# os2.net
KiCad netlist of a schematic drawn in EAGLE
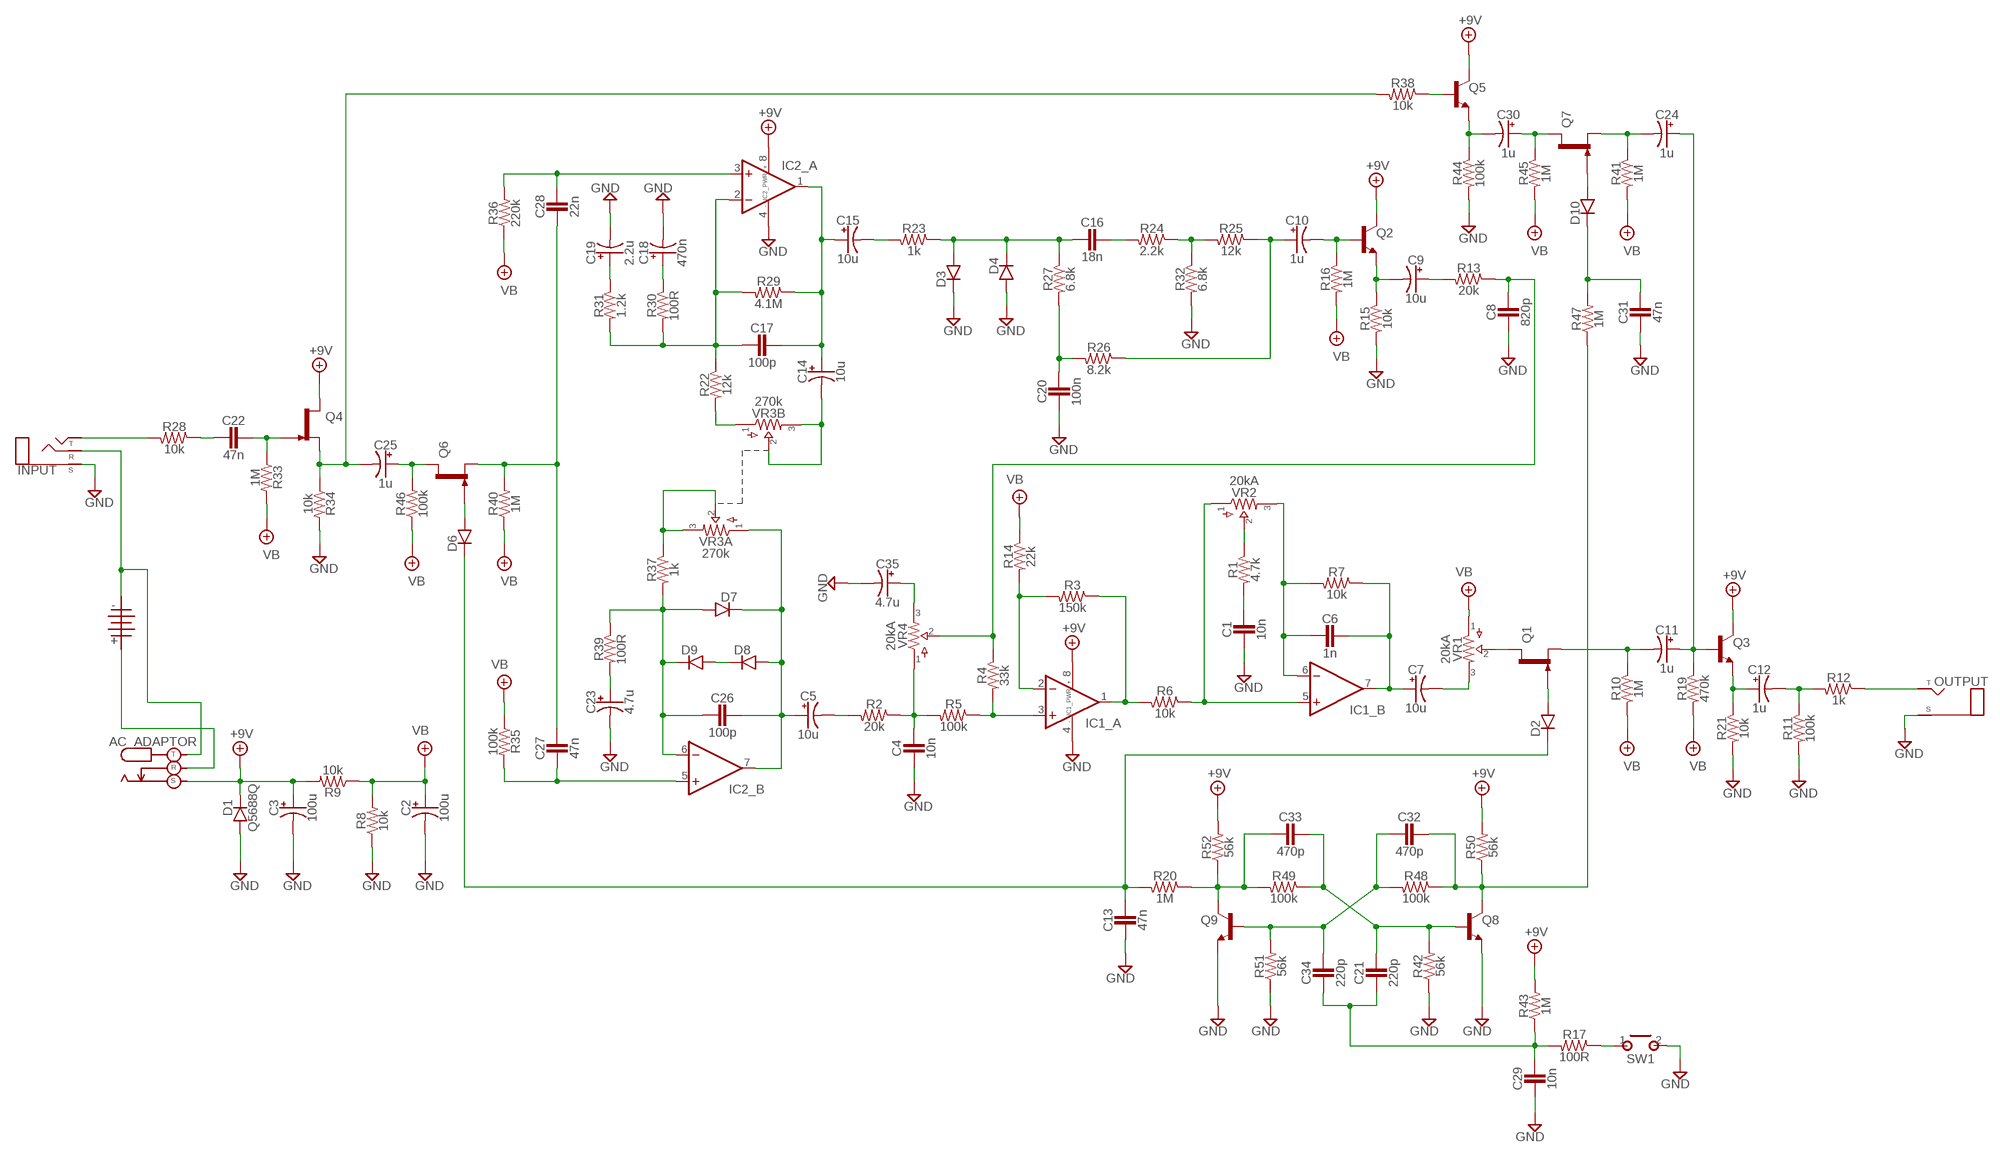
[diagram p0: schematic, sheet 1]

(export (version "E")
  (design (tool "Eeschema 10.0.6"))
  (components
    (comp (ref "1101")
      (value "BATTERY")
      (footprint "eagle-import:TWO_PADS")
      (libsource (lib "eagle-import") (part "BATTERY"))
    )
    (comp (ref "AC_ADAPTOR")
      (value "DC_KOBICONN")
      (footprint "eagle-import:DC_KOBICONN")
      (libsource (lib "eagle-import") (part "DC_KOBICONN"))
    )
    (comp (ref "C1")
      (value "10n")
      (footprint "eagle-import:BOX_SMALL")
      (libsource (lib "eagle-import") (part "CER/FILMBOX.1"))
    )
    (comp (ref "C2")
      (value "100u")
      (footprint "eagle-import:050_020")
      (libsource (lib "eagle-import") (part "0500"))
    )
    (comp (ref "C3")
      (value "100u")
      (footprint "eagle-import:050_020")
      (libsource (lib "eagle-import") (part "0500"))
    )
    (comp (ref "C4")
      (value "10n")
      (footprint "eagle-import:BOX_SMALL")
      (libsource (lib "eagle-import") (part "CER/FILMBOX.1"))
    )
    (comp (ref "C5")
      (value "10u")
      (footprint "eagle-import:050_020")
      (libsource (lib "eagle-import") (part "0500"))
    )
    (comp (ref "C6")
      (value "1n")
      (footprint "eagle-import:BOX_SMALL")
      (libsource (lib "eagle-import") (part "CER/FILMBOX.1"))
    )
    (comp (ref "C7")
      (value "10u")
      (footprint "eagle-import:050_020")
      (libsource (lib "eagle-import") (part "0500"))
    )
    (comp (ref "C8")
      (value "820p")
      (footprint "eagle-import:BOX_SMALL")
      (libsource (lib "eagle-import") (part "CER/FILMBOX.1"))
    )
    (comp (ref "C9")
      (value "10u")
      (footprint "eagle-import:050_020")
      (libsource (lib "eagle-import") (part "0500"))
    )
    (comp (ref "C10")
      (value "1u")
      (footprint "eagle-import:050_020")
      (libsource (lib "eagle-import") (part "0500"))
    )
    (comp (ref "C11")
      (value "1u")
      (footprint "eagle-import:050_020")
      (libsource (lib "eagle-import") (part "0500"))
    )
    (comp (ref "C12")
      (value "1u")
      (footprint "eagle-import:050_020")
      (libsource (lib "eagle-import") (part "0500"))
    )
    (comp (ref "C13")
      (value "47n")
      (footprint "eagle-import:BOX_SMALL")
      (libsource (lib "eagle-import") (part "CER/FILMBOX.1"))
    )
    (comp (ref "C14")
      (value "10u")
      (footprint "eagle-import:050_020")
      (libsource (lib "eagle-import") (part "0500"))
    )
    (comp (ref "C15")
      (value "10u")
      (footprint "eagle-import:050_020")
      (libsource (lib "eagle-import") (part "0500"))
    )
    (comp (ref "C16")
      (value "18n")
      (footprint "eagle-import:BOX_SMALL")
      (libsource (lib "eagle-import") (part "CER/FILMBOX.1"))
    )
    (comp (ref "C17")
      (value "100p")
      (footprint "eagle-import:BOX_SMALL")
      (libsource (lib "eagle-import") (part "CER/FILMBOX.1"))
    )
    (comp (ref "C18")
      (value "470n")
      (footprint "eagle-import:050_020")
      (libsource (lib "eagle-import") (part "0500"))
    )
    (comp (ref "C19")
      (value "2.2u")
      (footprint "eagle-import:050_020")
      (libsource (lib "eagle-import") (part "0500"))
    )
    (comp (ref "C20")
      (value "100n")
      (footprint "eagle-import:BOX_SMALL")
      (libsource (lib "eagle-import") (part "CER/FILMBOX.1"))
    )
    (comp (ref "C21")
      (value "220p")
      (footprint "eagle-import:BOX_SMALL")
      (libsource (lib "eagle-import") (part "CER/FILMBOX.1"))
    )
    (comp (ref "C22")
      (value "47n")
      (footprint "eagle-import:BOX_SMALL")
      (libsource (lib "eagle-import") (part "CER/FILMBOX.1"))
    )
    (comp (ref "C23")
      (value "4.7u")
      (footprint "eagle-import:050_020")
      (libsource (lib "eagle-import") (part "0500"))
    )
    (comp (ref "C24")
      (value "1u")
      (footprint "eagle-import:050_020")
      (libsource (lib "eagle-import") (part "0500"))
    )
    (comp (ref "C25")
      (value "1u")
      (footprint "eagle-import:050_020")
      (libsource (lib "eagle-import") (part "0500"))
    )
    (comp (ref "C26")
      (value "100p")
      (footprint "eagle-import:BOX_SMALL")
      (libsource (lib "eagle-import") (part "CER/FILMBOX.1"))
    )
    (comp (ref "C27")
      (value "47n")
      (footprint "eagle-import:BOX_SMALL")
      (libsource (lib "eagle-import") (part "CER/FILMBOX.1"))
    )
    (comp (ref "C28")
      (value "22n")
      (footprint "eagle-import:BOX_SMALL")
      (libsource (lib "eagle-import") (part "CER/FILMBOX.1"))
    )
    (comp (ref "C29")
      (value "10n")
      (footprint "eagle-import:BOX_SMALL")
      (libsource (lib "eagle-import") (part "CER/FILMBOX.1"))
    )
    (comp (ref "C30")
      (value "1u")
      (footprint "eagle-import:050_020")
      (libsource (lib "eagle-import") (part "0500"))
    )
    (comp (ref "C31")
      (value "47n")
      (footprint "eagle-import:BOX_SMALL")
      (libsource (lib "eagle-import") (part "CER/FILMBOX.1"))
    )
    (comp (ref "C32")
      (value "470p")
      (footprint "eagle-import:BOX_SMALL")
      (libsource (lib "eagle-import") (part "CER/FILMBOX.1"))
    )
    (comp (ref "C33")
      (value "470p")
      (footprint "eagle-import:BOX_SMALL")
      (libsource (lib "eagle-import") (part "CER/FILMBOX.1"))
    )
    (comp (ref "C34")
      (value "220p")
      (footprint "eagle-import:BOX_SMALL")
      (libsource (lib "eagle-import") (part "CER/FILMBOX.1"))
    )
    (comp (ref "C35")
      (value "4.7u")
      (footprint "eagle-import:050_020")
      (libsource (lib "eagle-import") (part "0500"))
    )
    (comp (ref "D1")
      (value "Q5688Q")
      (footprint "eagle-import:DO35-2")
      (libsource (lib "eagle-import") (part "DO35.2"))
    )
    (comp (ref "D2")
      (value "DO35.2")
      (footprint "eagle-import:DO35-2")
      (libsource (lib "eagle-import") (part "DO35.2"))
    )
    (comp (ref "D3")
      (value "DO35.2")
      (footprint "eagle-import:DO35-2")
      (libsource (lib "eagle-import") (part "DO35.2"))
    )
    (comp (ref "D4")
      (value "DO35.2")
      (footprint "eagle-import:DO35-2")
      (libsource (lib "eagle-import") (part "DO35.2"))
    )
    (comp (ref "D6")
      (value "DO35.2")
      (footprint "eagle-import:DO35-2")
      (libsource (lib "eagle-import") (part "DO35.2"))
    )
    (comp (ref "D7")
      (value "DO35.2")
      (footprint "eagle-import:DO35-2")
      (libsource (lib "eagle-import") (part "DO35.2"))
    )
    (comp (ref "D8")
      (value "DO35.2")
      (footprint "eagle-import:DO35-2")
      (libsource (lib "eagle-import") (part "DO35.2"))
    )
    (comp (ref "D9")
      (value "DO35.2")
      (footprint "eagle-import:DO35-2")
      (libsource (lib "eagle-import") (part "DO35.2"))
    )
    (comp (ref "D10")
      (value "DO35.2")
      (footprint "eagle-import:DO35-2")
      (libsource (lib "eagle-import") (part "DO35.2"))
    )
    (comp (ref "IC1")
      (value "DUALTH")
      (footprint "eagle-import:DIL0")
      (libsource (lib "eagle-import") (part "DUALTH"))
    )
    (comp (ref "IC2")
      (value "DUALTH")
      (footprint "eagle-import:DIL0")
      (libsource (lib "eagle-import") (part "DUALTH"))
    )
    (comp (ref "INPUT")
      (value "STEREO3PADS")
      (footprint "eagle-import:THREEPADS")
      (libsource (lib "eagle-import") (part "STEREO3PADS"))
    )
    (comp (ref "OUTPUT")
      (value "MONO")
      (footprint "eagle-import:TWO_PADS")
      (libsource (lib "eagle-import") (part "MONO"))
    )
    (comp (ref "Q1")
      (value "2N5457")
      (footprint "eagle-import:TO92-")
      (libsource (lib "eagle-import") (part "2N5457"))
    )
    (comp (ref "Q2")
      (value "2SC828A")
      (footprint "eagle-import:TO92-")
      (libsource (lib "eagle-import") (part "2SC828A"))
    )
    (comp (ref "Q3")
      (value "2SC828A")
      (footprint "eagle-import:TO92-")
      (libsource (lib "eagle-import") (part "2SC828A"))
    )
    (comp (ref "Q4")
      (value "2N5457")
      (footprint "eagle-import:TO92-")
      (libsource (lib "eagle-import") (part "2N5457"))
    )
    (comp (ref "Q5")
      (value "2SC828A")
      (footprint "eagle-import:TO92-")
      (libsource (lib "eagle-import") (part "2SC828A"))
    )
    (comp (ref "Q6")
      (value "2N5457")
      (footprint "eagle-import:TO92-")
      (libsource (lib "eagle-import") (part "2N5457"))
    )
    (comp (ref "Q7")
      (value "2N5457")
      (footprint "eagle-import:TO92-")
      (libsource (lib "eagle-import") (part "2N5457"))
    )
    (comp (ref "Q8")
      (value "2SC828A")
      (footprint "eagle-import:TO92-")
      (libsource (lib "eagle-import") (part "2SC828A"))
    )
    (comp (ref "Q9")
      (value "2SC828A")
      (footprint "eagle-import:TO92-")
      (libsource (lib "eagle-import") (part "2SC828A"))
    )
    (comp (ref "R1")
      (value "4.7k")
      (footprint "eagle-import:R0207_3")
      (libsource (lib "eagle-import") (part "R_.3B"))
    )
    (comp (ref "R2")
      (value "20k")
      (footprint "eagle-import:R0207_3")
      (libsource (lib "eagle-import") (part "R_.3B"))
    )
    (comp (ref "R3")
      (value "150k")
      (footprint "eagle-import:R0207_3")
      (libsource (lib "eagle-import") (part "R_.3B"))
    )
    (comp (ref "R4")
      (value "33k")
      (footprint "eagle-import:R0207_3")
      (libsource (lib "eagle-import") (part "R_.3B"))
    )
    (comp (ref "R5")
      (value "100k")
      (footprint "eagle-import:R0207_3")
      (libsource (lib "eagle-import") (part "R_.3B"))
    )
    (comp (ref "R6")
      (value "10k")
      (footprint "eagle-import:R0207_3")
      (libsource (lib "eagle-import") (part "R_.3B"))
    )
    (comp (ref "R7")
      (value "10k")
      (footprint "eagle-import:R0207_3")
      (libsource (lib "eagle-import") (part "R_.3B"))
    )
    (comp (ref "R8")
      (value "10k")
      (footprint "eagle-import:R0207_3")
      (libsource (lib "eagle-import") (part "R_.3B"))
    )
    (comp (ref "R9")
      (value "10k")
      (footprint "eagle-import:R0207_3")
      (libsource (lib "eagle-import") (part "R_.3B"))
    )
    (comp (ref "R10")
      (value "1M")
      (footprint "eagle-import:R0207_3")
      (libsource (lib "eagle-import") (part "R_.3B"))
    )
    (comp (ref "R11")
      (value "100k")
      (footprint "eagle-import:R0207_3")
      (libsource (lib "eagle-import") (part "R_.3B"))
    )
    (comp (ref "R12")
      (value "1k")
      (footprint "eagle-import:R0207_3")
      (libsource (lib "eagle-import") (part "R_.3B"))
    )
    (comp (ref "R13")
      (value "20k")
      (footprint "eagle-import:R0207_3")
      (libsource (lib "eagle-import") (part "R_.3B"))
    )
    (comp (ref "R14")
      (value "22k")
      (footprint "eagle-import:R0207_3")
      (libsource (lib "eagle-import") (part "R_.3B"))
    )
    (comp (ref "R15")
      (value "10k")
      (footprint "eagle-import:R0207_3")
      (libsource (lib "eagle-import") (part "R_.3B"))
    )
    (comp (ref "R16")
      (value "1M")
      (footprint "eagle-import:R0207_3")
      (libsource (lib "eagle-import") (part "R_.3B"))
    )
    (comp (ref "R17")
      (value "100R")
      (footprint "eagle-import:R0207_3")
      (libsource (lib "eagle-import") (part "R_.3B"))
    )
    (comp (ref "R19")
      (value "470k")
      (footprint "eagle-import:R0207_3")
      (libsource (lib "eagle-import") (part "R_.3B"))
    )
    (comp (ref "R20")
      (value "1M")
      (footprint "eagle-import:R0207_3")
      (libsource (lib "eagle-import") (part "R_.3B"))
    )
    (comp (ref "R21")
      (value "10k")
      (footprint "eagle-import:R0207_3")
      (libsource (lib "eagle-import") (part "R_.3B"))
    )
    (comp (ref "R22")
      (value "12k")
      (footprint "eagle-import:R0207_3")
      (libsource (lib "eagle-import") (part "R_.3B"))
    )
    (comp (ref "R23")
      (value "1k")
      (footprint "eagle-import:R0207_3")
      (libsource (lib "eagle-import") (part "R_.3B"))
    )
    (comp (ref "R24")
      (value "2.2k")
      (footprint "eagle-import:R0207_3")
      (libsource (lib "eagle-import") (part "R_.3B"))
    )
    (comp (ref "R25")
      (value "12k")
      (footprint "eagle-import:R0207_3")
      (libsource (lib "eagle-import") (part "R_.3B"))
    )
    (comp (ref "R26")
      (value "8.2k")
      (footprint "eagle-import:R0207_3")
      (libsource (lib "eagle-import") (part "R_.3B"))
    )
    (comp (ref "R27")
      (value "6.8k")
      (footprint "eagle-import:R0207_3")
      (libsource (lib "eagle-import") (part "R_.3B"))
    )
    (comp (ref "R28")
      (value "10k")
      (footprint "eagle-import:R0207_3")
      (libsource (lib "eagle-import") (part "R_.3B"))
    )
    (comp (ref "R29")
      (value "4.1M")
      (footprint "eagle-import:R0207_3")
      (libsource (lib "eagle-import") (part "R_.3B"))
    )
    (comp (ref "R30")
      (value "100R")
      (footprint "eagle-import:R0207_3")
      (libsource (lib "eagle-import") (part "R_.3B"))
    )
    (comp (ref "R31")
      (value "1.2k")
      (footprint "eagle-import:R0207_3")
      (libsource (lib "eagle-import") (part "R_.3B"))
    )
    (comp (ref "R32")
      (value "6.8k")
      (footprint "eagle-import:R0207_3")
      (libsource (lib "eagle-import") (part "R_.3B"))
    )
    (comp (ref "R33")
      (value "1M")
      (footprint "eagle-import:R0207_3")
      (libsource (lib "eagle-import") (part "R_.3B"))
    )
    (comp (ref "R34")
      (value "10k")
      (footprint "eagle-import:R0207_3")
      (libsource (lib "eagle-import") (part "R_.3B"))
    )
    (comp (ref "R35")
      (value "100k")
      (footprint "eagle-import:R0207_3")
      (libsource (lib "eagle-import") (part "R_.3B"))
    )
    (comp (ref "R36")
      (value "220k")
      (footprint "eagle-import:R0207_3")
      (libsource (lib "eagle-import") (part "R_.3B"))
    )
    (comp (ref "R37")
      (value "1k")
      (footprint "eagle-import:R0207_3")
      (libsource (lib "eagle-import") (part "R_.3B"))
    )
    (comp (ref "R38")
      (value "10k")
      (footprint "eagle-import:R0207_3")
      (libsource (lib "eagle-import") (part "R_.3B"))
    )
    (comp (ref "R39")
      (value "100R")
      (footprint "eagle-import:R0207_3")
      (libsource (lib "eagle-import") (part "R_.3B"))
    )
    (comp (ref "R40")
      (value "1M")
      (footprint "eagle-import:R0207_3")
      (libsource (lib "eagle-import") (part "R_.3B"))
    )
    (comp (ref "R41")
      (value "1M")
      (footprint "eagle-import:R0207_3")
      (libsource (lib "eagle-import") (part "R_.3B"))
    )
    (comp (ref "R42")
      (value "56k")
      (footprint "eagle-import:R0207_3")
      (libsource (lib "eagle-import") (part "R_.3B"))
    )
    (comp (ref "R43")
      (value "1M")
      (footprint "eagle-import:R0207_3")
      (libsource (lib "eagle-import") (part "R_.3B"))
    )
    (comp (ref "R44")
      (value "100k")
      (footprint "eagle-import:R0207_3")
      (libsource (lib "eagle-import") (part "R_.3B"))
    )
    (comp (ref "R45")
      (value "1M")
      (footprint "eagle-import:R0207_3")
      (libsource (lib "eagle-import") (part "R_.3B"))
    )
    (comp (ref "R46")
      (value "100k")
      (footprint "eagle-import:R0207_3")
      (libsource (lib "eagle-import") (part "R_.3B"))
    )
    (comp (ref "R47")
      (value "1M")
      (footprint "eagle-import:R0207_3")
      (libsource (lib "eagle-import") (part "R_.3B"))
    )
    (comp (ref "R48")
      (value "100k")
      (footprint "eagle-import:R0207_3")
      (libsource (lib "eagle-import") (part "R_.3B"))
    )
    (comp (ref "R49")
      (value "100k")
      (footprint "eagle-import:R0207_3")
      (libsource (lib "eagle-import") (part "R_.3B"))
    )
    (comp (ref "R50")
      (value "56k")
      (footprint "eagle-import:R0207_3")
      (libsource (lib "eagle-import") (part "R_.3B"))
    )
    (comp (ref "R51")
      (value "56k")
      (footprint "eagle-import:R0207_3")
      (libsource (lib "eagle-import") (part "R_.3B"))
    )
    (comp (ref "R52")
      (value "56k")
      (footprint "eagle-import:R0207_3")
      (libsource (lib "eagle-import") (part "R_.3B"))
    )
    (comp (ref "SW1")
      (value "MOMENTARY")
      (footprint "eagle-import:SPST")
      (libsource (lib "eagle-import") (part "MOMENTARY"))
    )
    (comp (ref "VR1")
      (value "20kA")
      (footprint "eagle-import:16MM")
      (libsource (lib "eagle-import") (part "POTS16MM"))
    )
    (comp (ref "VR2")
      (value "20kA")
      (footprint "eagle-import:16MM")
      (libsource (lib "eagle-import") (part "POTS16MM"))
    )
    (comp (ref "VR3A")
      (value "270k")
      (footprint "eagle-import:16MM")
      (libsource (lib "eagle-import") (part "POTS16MM"))
    )
    (comp (ref "VR3B")
      (value "270k")
      (footprint "eagle-import:16MM")
      (libsource (lib "eagle-import") (part "POTS16MM"))
    )
    (comp (ref "VR4")
      (value "20kA")
      (footprint "eagle-import:16MM")
      (libsource (lib "eagle-import") (part "POTS16MM"))
    )
  )
  (nets
    (net (code "1") (name "+9V") (class "Default")
      (node (ref "AC_ADAPTOR") (pin "S") (pinfunction "S_S") (pintype "bidirectional"))
      (node (ref "C3") (pin "+") (pinfunction "+_+") (pintype "passive"))
      (node (ref "D1") (pin "C") (pinfunction "C_C") (pintype "passive"))
      (node (ref "IC1") (pin "8") (pinfunction "V+_8") (pintype "power_in"))
      (node (ref "IC2") (pin "8") (pinfunction "V+_8") (pintype "power_in"))
      (node (ref "Q2") (pin "2") (pinfunction "C_2") (pintype "passive"))
      (node (ref "Q3") (pin "2") (pinfunction "C_2") (pintype "passive"))
      (node (ref "Q4") (pin "3") (pinfunction "D_3") (pintype "passive"))
      (node (ref "Q5") (pin "2") (pinfunction "C_2") (pintype "passive"))
      (node (ref "R43") (pin "2") (pinfunction "2_2") (pintype "passive"))
      (node (ref "R50") (pin "2") (pinfunction "2_2") (pintype "passive"))
      (node (ref "R52") (pin "2") (pinfunction "2_2") (pintype "passive"))
      (node (ref "R9") (pin "2") (pinfunction "2_2") (pintype "passive"))
    )
    (net (code "2") (name "GND") (class "Default")
      (node (ref "C1") (pin "2") (pinfunction "2_2") (pintype "passive"))
      (node (ref "C13") (pin "1") (pinfunction "1_1") (pintype "passive"))
      (node (ref "C18") (pin "-") (pinfunction "-_-") (pintype "passive"))
      (node (ref "C19") (pin "-") (pinfunction "-_-") (pintype "passive"))
      (node (ref "C2") (pin "-") (pinfunction "-_-") (pintype "passive"))
      (node (ref "C20") (pin "2") (pinfunction "2_2") (pintype "passive"))
      (node (ref "C23") (pin "-") (pinfunction "-_-") (pintype "passive"))
      (node (ref "C29") (pin "1") (pinfunction "1_1") (pintype "passive"))
      (node (ref "C3") (pin "-") (pinfunction "-_-") (pintype "passive"))
      (node (ref "C31") (pin "2") (pinfunction "2_2") (pintype "passive"))
      (node (ref "C35") (pin "-") (pinfunction "-_-") (pintype "passive"))
      (node (ref "C4") (pin "2") (pinfunction "2_2") (pintype "passive"))
      (node (ref "C8") (pin "2") (pinfunction "2_2") (pintype "passive"))
      (node (ref "D1") (pin "A") (pinfunction "A_A") (pintype "passive"))
      (node (ref "D3") (pin "C") (pinfunction "C_C") (pintype "passive"))
      (node (ref "D4") (pin "A") (pinfunction "A_A") (pintype "passive"))
      (node (ref "IC1") (pin "4") (pinfunction "V-_4") (pintype "power_in"))
      (node (ref "IC2") (pin "4") (pinfunction "V-_4") (pintype "power_in"))
      (node (ref "INPUT") (pin "SLEEVE") (pinfunction "S_SLEEVE") (pintype "passive"))
      (node (ref "OUTPUT") (pin "S") (pinfunction "SLEEVE_S") (pintype "passive"))
      (node (ref "Q8") (pin "3") (pinfunction "E_3") (pintype "passive"))
      (node (ref "Q9") (pin "3") (pinfunction "E_3") (pintype "passive"))
      (node (ref "R11") (pin "2") (pinfunction "2_2") (pintype "passive"))
      (node (ref "R15") (pin "2") (pinfunction "2_2") (pintype "passive"))
      (node (ref "R21") (pin "2") (pinfunction "2_2") (pintype "passive"))
      (node (ref "R32") (pin "2") (pinfunction "2_2") (pintype "passive"))
      (node (ref "R34") (pin "2") (pinfunction "2_2") (pintype "passive"))
      (node (ref "R42") (pin "1") (pinfunction "1_1") (pintype "passive"))
      (node (ref "R44") (pin "2") (pinfunction "2_2") (pintype "passive"))
      (node (ref "R51") (pin "1") (pinfunction "1_1") (pintype "passive"))
      (node (ref "R8") (pin "1") (pinfunction "1_1") (pintype "passive"))
      (node (ref "SW1") (pin "2") (pinfunction "S_2") (pintype "passive"))
    )
    (net (code "3") (name "Net-(1101-P$1)") (class "Default")
      (node (ref "1101") (pin "T") (pinfunction "P$1_T") (pintype "bidirectional"))
      (node (ref "AC_ADAPTOR") (pin "R") (pinfunction "R_R") (pintype "bidirectional"))
    )
    (net (code "4") (name "Net-(1101-P$2)") (class "Default")
      (node (ref "1101") (pin "S") (pinfunction "P$2_S") (pintype "bidirectional"))
      (node (ref "AC_ADAPTOR") (pin "T") (pinfunction "T_T") (pintype "bidirectional"))
      (node (ref "INPUT") (pin "RING") (pinfunction "R_RING") (pintype "passive"))
    )
    (net (code "5") (name "Net-(C1-Pad1)") (class "Default")
      (node (ref "C1") (pin "1") (pinfunction "1_1") (pintype "passive"))
      (node (ref "R1") (pin "2") (pinfunction "2_2") (pintype "passive"))
    )
    (net (code "6") (name "Net-(C4-Pad1)") (class "Default")
      (node (ref "C4") (pin "1") (pinfunction "1_1") (pintype "passive"))
      (node (ref "R2") (pin "1") (pinfunction "1_1") (pintype "passive"))
      (node (ref "R5") (pin "2") (pinfunction "2_2") (pintype "passive"))
      (node (ref "VR4") (pin "1") (pinfunction "1_1") (pintype "passive"))
    )
    (net (code "7") (name "Net-(C5-Pad-)") (class "Default")
      (node (ref "C5") (pin "-") (pinfunction "-_-") (pintype "passive"))
      (node (ref "R2") (pin "2") (pinfunction "2_2") (pintype "passive"))
    )
    (net (code "8") (name "Net-(C7-Pad-)") (class "Default")
      (node (ref "C7") (pin "-") (pinfunction "-_-") (pintype "passive"))
      (node (ref "VR1") (pin "3") (pinfunction "3_3") (pintype "passive"))
    )
    (net (code "9") (name "Net-(C8-Pad1)") (class "Default")
      (node (ref "C8") (pin "1") (pinfunction "1_1") (pintype "passive"))
      (node (ref "R13") (pin "1") (pinfunction "1_1") (pintype "passive"))
      (node (ref "R4") (pin "1") (pinfunction "1_1") (pintype "passive"))
      (node (ref "VR4") (pin "2") (pinfunction "2_2") (pintype "passive"))
    )
    (net (code "10") (name "Net-(C9-Pad+)") (class "Default")
      (node (ref "C9") (pin "+") (pinfunction "+_+") (pintype "passive"))
      (node (ref "R13") (pin "2") (pinfunction "2_2") (pintype "passive"))
    )
    (net (code "11") (name "Net-(C10-Pad+)") (class "Default")
      (node (ref "C10") (pin "+") (pinfunction "+_+") (pintype "passive"))
      (node (ref "R25") (pin "1") (pinfunction "1_1") (pintype "passive"))
      (node (ref "R26") (pin "1") (pinfunction "1_1") (pintype "passive"))
    )
    (net (code "12") (name "Net-(C12-Pad-)") (class "Default")
      (node (ref "C12") (pin "-") (pinfunction "-_-") (pintype "passive"))
      (node (ref "R11") (pin "1") (pinfunction "1_1") (pintype "passive"))
      (node (ref "R12") (pin "2") (pinfunction "2_2") (pintype "passive"))
    )
    (net (code "13") (name "Net-(C13-Pad2)") (class "Default")
      (node (ref "C13") (pin "2") (pinfunction "2_2") (pintype "passive"))
      (node (ref "D2") (pin "C") (pinfunction "C_C") (pintype "passive"))
      (node (ref "D6") (pin "C") (pinfunction "C_C") (pintype "passive"))
      (node (ref "R20") (pin "2") (pinfunction "2_2") (pintype "passive"))
    )
    (net (code "14") (name "Net-(C14-Pad-)") (class "Default")
      (node (ref "C14") (pin "-") (pinfunction "-_-") (pintype "passive"))
      (node (ref "VR3B") (pin "2") (pinfunction "2_2") (pintype "passive"))
      (node (ref "VR3B") (pin "3") (pinfunction "3_3") (pintype "passive"))
    )
    (net (code "15") (name "Net-(C15-Pad-)") (class "Default")
      (node (ref "C15") (pin "-") (pinfunction "-_-") (pintype "passive"))
      (node (ref "R23") (pin "2") (pinfunction "2_2") (pintype "passive"))
    )
    (net (code "16") (name "Net-(C16-Pad1)") (class "Default")
      (node (ref "C16") (pin "1") (pinfunction "1_1") (pintype "passive"))
      (node (ref "R24") (pin "2") (pinfunction "2_2") (pintype "passive"))
    )
    (net (code "17") (name "Net-(C16-Pad2)") (class "Default")
      (node (ref "C16") (pin "2") (pinfunction "2_2") (pintype "passive"))
      (node (ref "D3") (pin "A") (pinfunction "A_A") (pintype "passive"))
      (node (ref "D4") (pin "C") (pinfunction "C_C") (pintype "passive"))
      (node (ref "R23") (pin "1") (pinfunction "1_1") (pintype "passive"))
      (node (ref "R27") (pin "1") (pinfunction "1_1") (pintype "passive"))
    )
    (net (code "18") (name "Net-(C18-Pad+)") (class "Default")
      (node (ref "C18") (pin "+") (pinfunction "+_+") (pintype "passive"))
      (node (ref "R30") (pin "1") (pinfunction "1_1") (pintype "passive"))
    )
    (net (code "19") (name "Net-(C19-Pad+)") (class "Default")
      (node (ref "C19") (pin "+") (pinfunction "+_+") (pintype "passive"))
      (node (ref "R31") (pin "1") (pinfunction "1_1") (pintype "passive"))
    )
    (net (code "20") (name "Net-(C20-Pad1)") (class "Default")
      (node (ref "C20") (pin "1") (pinfunction "1_1") (pintype "passive"))
      (node (ref "R26") (pin "2") (pinfunction "2_2") (pintype "passive"))
      (node (ref "R27") (pin "2") (pinfunction "2_2") (pintype "passive"))
    )
    (net (code "21") (name "Net-(C21-Pad2)") (class "Default")
      (node (ref "C21") (pin "2") (pinfunction "2_2") (pintype "passive"))
      (node (ref "C29") (pin "2") (pinfunction "2_2") (pintype "passive"))
      (node (ref "C34") (pin "2") (pinfunction "2_2") (pintype "passive"))
      (node (ref "R17") (pin "2") (pinfunction "2_2") (pintype "passive"))
      (node (ref "R43") (pin "1") (pinfunction "1_1") (pintype "passive"))
    )
    (net (code "22") (name "Net-(C22-Pad2)") (class "Default")
      (node (ref "C22") (pin "2") (pinfunction "2_2") (pintype "passive"))
      (node (ref "R28") (pin "1") (pinfunction "1_1") (pintype "passive"))
    )
    (net (code "23") (name "Net-(C23-Pad+)") (class "Default")
      (node (ref "C23") (pin "+") (pinfunction "+_+") (pintype "passive"))
      (node (ref "R39") (pin "2") (pinfunction "2_2") (pintype "passive"))
    )
    (net (code "24") (name "Net-(C31-Pad1)") (class "Default")
      (node (ref "C31") (pin "1") (pinfunction "1_1") (pintype "passive"))
      (node (ref "D10") (pin "C") (pinfunction "C_C") (pintype "passive"))
      (node (ref "R47") (pin "2") (pinfunction "2_2") (pintype "passive"))
    )
    (net (code "25") (name "Net-(C35-Pad+)") (class "Default")
      (node (ref "C35") (pin "+") (pinfunction "+_+") (pintype "passive"))
      (node (ref "VR4") (pin "3") (pinfunction "3_3") (pintype "passive"))
    )
    (net (code "26") (name "Net-(D8-PadC)") (class "Default")
      (node (ref "D8") (pin "C") (pinfunction "C_C") (pintype "passive"))
      (node (ref "D9") (pin "A") (pinfunction "A_A") (pintype "passive"))
    )
    (net (code "27") (name "Net-(IC1A-+IN)") (class "Default")
      (node (ref "IC1") (pin "3") (pinfunction "+IN_3") (pintype "input"))
      (node (ref "R4") (pin "2") (pinfunction "2_2") (pintype "passive"))
      (node (ref "R5") (pin "1") (pinfunction "1_1") (pintype "passive"))
    )
    (net (code "28") (name "Net-(IC1A--IN)") (class "Default")
      (node (ref "IC1") (pin "2") (pinfunction "-IN_2") (pintype "input"))
      (node (ref "R14") (pin "2") (pinfunction "2_2") (pintype "passive"))
      (node (ref "R3") (pin "2") (pinfunction "2_2") (pintype "passive"))
    )
    (net (code "29") (name "Net-(IC1A-OUT)") (class "Default")
      (node (ref "IC1") (pin "1") (pinfunction "OUT_1") (pintype "output"))
      (node (ref "R3") (pin "1") (pinfunction "1_1") (pintype "passive"))
      (node (ref "R6") (pin "2") (pinfunction "2_2") (pintype "passive"))
    )
    (net (code "30") (name "Net-(IC1B-+IN)") (class "Default")
      (node (ref "IC1") (pin "5") (pinfunction "+IN_5") (pintype "input"))
      (node (ref "R6") (pin "1") (pinfunction "1_1") (pintype "passive"))
      (node (ref "VR2") (pin "1") (pinfunction "1_1") (pintype "passive"))
    )
    (net (code "31") (name "Net-(IC1B--IN)") (class "Default")
      (node (ref "C6") (pin "2") (pinfunction "2_2") (pintype "passive"))
      (node (ref "IC1") (pin "6") (pinfunction "-IN_6") (pintype "input"))
      (node (ref "R7") (pin "2") (pinfunction "2_2") (pintype "passive"))
      (node (ref "VR2") (pin "3") (pinfunction "3_3") (pintype "passive"))
    )
    (net (code "32") (name "Net-(IC1B-OUT)") (class "Default")
      (node (ref "C6") (pin "1") (pinfunction "1_1") (pintype "passive"))
      (node (ref "C7") (pin "+") (pinfunction "+_+") (pintype "passive"))
      (node (ref "IC1") (pin "7") (pinfunction "OUT_7") (pintype "output"))
      (node (ref "R7") (pin "1") (pinfunction "1_1") (pintype "passive"))
    )
    (net (code "33") (name "Net-(IC2A-+IN)") (class "Default")
      (node (ref "C28") (pin "1") (pinfunction "1_1") (pintype "passive"))
      (node (ref "IC2") (pin "3") (pinfunction "+IN_3") (pintype "input"))
      (node (ref "R36") (pin "2") (pinfunction "2_2") (pintype "passive"))
    )
    (net (code "34") (name "Net-(IC2A--IN)") (class "Default")
      (node (ref "C17") (pin "2") (pinfunction "2_2") (pintype "passive"))
      (node (ref "IC2") (pin "2") (pinfunction "-IN_2") (pintype "input"))
      (node (ref "R22") (pin "1") (pinfunction "1_1") (pintype "passive"))
      (node (ref "R29") (pin "2") (pinfunction "2_2") (pintype "passive"))
      (node (ref "R30") (pin "2") (pinfunction "2_2") (pintype "passive"))
      (node (ref "R31") (pin "2") (pinfunction "2_2") (pintype "passive"))
    )
    (net (code "35") (name "Net-(IC2A-OUT)") (class "Default")
      (node (ref "C14") (pin "+") (pinfunction "+_+") (pintype "passive"))
      (node (ref "C15") (pin "+") (pinfunction "+_+") (pintype "passive"))
      (node (ref "C17") (pin "1") (pinfunction "1_1") (pintype "passive"))
      (node (ref "IC2") (pin "1") (pinfunction "OUT_1") (pintype "output"))
      (node (ref "R29") (pin "1") (pinfunction "1_1") (pintype "passive"))
    )
    (net (code "36") (name "Net-(IC2B-+IN)") (class "Default")
      (node (ref "C27") (pin "2") (pinfunction "2_2") (pintype "passive"))
      (node (ref "IC2") (pin "5") (pinfunction "+IN_5") (pintype "input"))
      (node (ref "R35") (pin "2") (pinfunction "2_2") (pintype "passive"))
    )
    (net (code "37") (name "Net-(IC2B--IN)") (class "Default")
      (node (ref "C26") (pin "2") (pinfunction "2_2") (pintype "passive"))
      (node (ref "D7") (pin "A") (pinfunction "A_A") (pintype "passive"))
      (node (ref "D9") (pin "C") (pinfunction "C_C") (pintype "passive"))
      (node (ref "IC2") (pin "6") (pinfunction "-IN_6") (pintype "input"))
      (node (ref "R37") (pin "2") (pinfunction "2_2") (pintype "passive"))
      (node (ref "R39") (pin "1") (pinfunction "1_1") (pintype "passive"))
    )
    (net (code "38") (name "Net-(IC2B-OUT)") (class "Default")
      (node (ref "C26") (pin "1") (pinfunction "1_1") (pintype "passive"))
      (node (ref "C5") (pin "+") (pinfunction "+_+") (pintype "passive"))
      (node (ref "D7") (pin "C") (pinfunction "C_C") (pintype "passive"))
      (node (ref "D8") (pin "A") (pinfunction "A_A") (pintype "passive"))
      (node (ref "IC2") (pin "7") (pinfunction "OUT_7") (pintype "output"))
      (node (ref "VR3A") (pin "1") (pinfunction "1_1") (pintype "passive"))
    )
    (net (code "39") (name "Net-(INPUT-T)") (class "Default")
      (node (ref "INPUT") (pin "TIP") (pinfunction "T_TIP") (pintype "passive"))
      (node (ref "R28") (pin "2") (pinfunction "2_2") (pintype "passive"))
    )
    (net (code "40") (name "Net-(OUTPUT-TIP)") (class "Default")
      (node (ref "OUTPUT") (pin "T") (pinfunction "TIP_T") (pintype "passive"))
      (node (ref "R12") (pin "1") (pinfunction "1_1") (pintype "passive"))
    )
    (net (code "41") (name "Net-(Q1-D)") (class "Default")
      (node (ref "Q1") (pin "3") (pinfunction "D_3") (pintype "passive"))
      (node (ref "VR1") (pin "2") (pinfunction "2_2") (pintype "passive"))
    )
    (net (code "42") (name "Net-(Q1-G)") (class "Default")
      (node (ref "D2") (pin "A") (pinfunction "A_A") (pintype "passive"))
      (node (ref "Q1") (pin "1") (pinfunction "G_1") (pintype "passive"))
    )
    (net (code "43") (name "Net-(Q1-S)") (class "Default")
      (node (ref "C11") (pin "-") (pinfunction "-_-") (pintype "passive"))
      (node (ref "Q1") (pin "2") (pinfunction "S_2") (pintype "passive"))
      (node (ref "R10") (pin "1") (pinfunction "1_1") (pintype "passive"))
    )
    (net (code "44") (name "Net-(Q2-B)") (class "Default")
      (node (ref "C10") (pin "-") (pinfunction "-_-") (pintype "passive"))
      (node (ref "Q2") (pin "1") (pinfunction "B_1") (pintype "passive"))
      (node (ref "R16") (pin "1") (pinfunction "1_1") (pintype "passive"))
    )
    (net (code "45") (name "Net-(Q2-E)") (class "Default")
      (node (ref "C9") (pin "-") (pinfunction "-_-") (pintype "passive"))
      (node (ref "Q2") (pin "3") (pinfunction "E_3") (pintype "passive"))
      (node (ref "R15") (pin "1") (pinfunction "1_1") (pintype "passive"))
    )
    (net (code "46") (name "Net-(Q3-B)") (class "Default")
      (node (ref "C11") (pin "+") (pinfunction "+_+") (pintype "passive"))
      (node (ref "C24") (pin "+") (pinfunction "+_+") (pintype "passive"))
      (node (ref "Q3") (pin "1") (pinfunction "B_1") (pintype "passive"))
      (node (ref "R19") (pin "1") (pinfunction "1_1") (pintype "passive"))
    )
    (net (code "47") (name "Net-(Q3-E)") (class "Default")
      (node (ref "C12") (pin "+") (pinfunction "+_+") (pintype "passive"))
      (node (ref "Q3") (pin "3") (pinfunction "E_3") (pintype "passive"))
      (node (ref "R21") (pin "1") (pinfunction "1_1") (pintype "passive"))
    )
    (net (code "48") (name "Net-(Q4-G)") (class "Default")
      (node (ref "C22") (pin "1") (pinfunction "1_1") (pintype "passive"))
      (node (ref "Q4") (pin "1") (pinfunction "G_1") (pintype "passive"))
      (node (ref "R33") (pin "1") (pinfunction "1_1") (pintype "passive"))
    )
    (net (code "49") (name "Net-(Q4-S)") (class "Default")
      (node (ref "C25") (pin "-") (pinfunction "-_-") (pintype "passive"))
      (node (ref "Q4") (pin "2") (pinfunction "S_2") (pintype "passive"))
      (node (ref "R34") (pin "1") (pinfunction "1_1") (pintype "passive"))
      (node (ref "R38") (pin "2") (pinfunction "2_2") (pintype "passive"))
    )
    (net (code "50") (name "Net-(Q5-B)") (class "Default")
      (node (ref "Q5") (pin "1") (pinfunction "B_1") (pintype "passive"))
      (node (ref "R38") (pin "1") (pinfunction "1_1") (pintype "passive"))
    )
    (net (code "51") (name "Net-(Q5-E)") (class "Default")
      (node (ref "C30") (pin "-") (pinfunction "-_-") (pintype "passive"))
      (node (ref "Q5") (pin "3") (pinfunction "E_3") (pintype "passive"))
      (node (ref "R44") (pin "1") (pinfunction "1_1") (pintype "passive"))
    )
    (net (code "52") (name "Net-(Q6-D)") (class "Default")
      (node (ref "C25") (pin "+") (pinfunction "+_+") (pintype "passive"))
      (node (ref "Q6") (pin "3") (pinfunction "D_3") (pintype "passive"))
      (node (ref "R46") (pin "2") (pinfunction "2_2") (pintype "passive"))
    )
    (net (code "53") (name "Net-(Q6-G)") (class "Default")
      (node (ref "D6") (pin "A") (pinfunction "A_A") (pintype "passive"))
      (node (ref "Q6") (pin "1") (pinfunction "G_1") (pintype "passive"))
    )
    (net (code "54") (name "Net-(Q6-S)") (class "Default")
      (node (ref "C27") (pin "1") (pinfunction "1_1") (pintype "passive"))
      (node (ref "C28") (pin "2") (pinfunction "2_2") (pintype "passive"))
      (node (ref "Q6") (pin "2") (pinfunction "S_2") (pintype "passive"))
      (node (ref "R40") (pin "2") (pinfunction "2_2") (pintype "passive"))
    )
    (net (code "55") (name "Net-(Q7-D)") (class "Default")
      (node (ref "C30") (pin "+") (pinfunction "+_+") (pintype "passive"))
      (node (ref "Q7") (pin "3") (pinfunction "D_3") (pintype "passive"))
      (node (ref "R45") (pin "1") (pinfunction "1_1") (pintype "passive"))
    )
    (net (code "56") (name "Net-(Q7-G)") (class "Default")
      (node (ref "D10") (pin "A") (pinfunction "A_A") (pintype "passive"))
      (node (ref "Q7") (pin "1") (pinfunction "G_1") (pintype "passive"))
    )
    (net (code "57") (name "Net-(Q7-S)") (class "Default")
      (node (ref "C24") (pin "-") (pinfunction "-_-") (pintype "passive"))
      (node (ref "Q7") (pin "2") (pinfunction "S_2") (pintype "passive"))
      (node (ref "R41") (pin "1") (pinfunction "1_1") (pintype "passive"))
    )
    (net (code "58") (name "Net-(Q8-B)") (class "Default")
      (node (ref "C21") (pin "1") (pinfunction "1_1") (pintype "passive"))
      (node (ref "C33") (pin "2") (pinfunction "2_2") (pintype "passive"))
      (node (ref "Q8") (pin "1") (pinfunction "B_1") (pintype "passive"))
      (node (ref "R42") (pin "2") (pinfunction "2_2") (pintype "passive"))
      (node (ref "R49") (pin "1") (pinfunction "1_1") (pintype "passive"))
    )
    (net (code "59") (name "Net-(Q8-C)") (class "Default")
      (node (ref "C32") (pin "2") (pinfunction "2_2") (pintype "passive"))
      (node (ref "Q8") (pin "2") (pinfunction "C_2") (pintype "passive"))
      (node (ref "R47") (pin "1") (pinfunction "1_1") (pintype "passive"))
      (node (ref "R48") (pin "1") (pinfunction "1_1") (pintype "passive"))
      (node (ref "R50") (pin "1") (pinfunction "1_1") (pintype "passive"))
    )
    (net (code "60") (name "Net-(Q9-B)") (class "Default")
      (node (ref "C32") (pin "1") (pinfunction "1_1") (pintype "passive"))
      (node (ref "C34") (pin "1") (pinfunction "1_1") (pintype "passive"))
      (node (ref "Q9") (pin "1") (pinfunction "B_1") (pintype "passive"))
      (node (ref "R48") (pin "2") (pinfunction "2_2") (pintype "passive"))
      (node (ref "R51") (pin "2") (pinfunction "2_2") (pintype "passive"))
    )
    (net (code "61") (name "Net-(Q9-C)") (class "Default")
      (node (ref "C33") (pin "1") (pinfunction "1_1") (pintype "passive"))
      (node (ref "Q9") (pin "2") (pinfunction "C_2") (pintype "passive"))
      (node (ref "R20") (pin "1") (pinfunction "1_1") (pintype "passive"))
      (node (ref "R49") (pin "2") (pinfunction "2_2") (pintype "passive"))
      (node (ref "R52") (pin "1") (pinfunction "1_1") (pintype "passive"))
    )
    (net (code "62") (name "Net-(R1-Pad1)") (class "Default")
      (node (ref "R1") (pin "1") (pinfunction "1_1") (pintype "passive"))
      (node (ref "VR2") (pin "2") (pinfunction "2_2") (pintype "passive"))
    )
    (net (code "63") (name "Net-(R22-Pad2)") (class "Default")
      (node (ref "R22") (pin "2") (pinfunction "2_2") (pintype "passive"))
      (node (ref "VR3B") (pin "1") (pinfunction "1_1") (pintype "passive"))
    )
    (net (code "64") (name "Net-(R24-Pad1)") (class "Default")
      (node (ref "R24") (pin "1") (pinfunction "1_1") (pintype "passive"))
      (node (ref "R25") (pin "2") (pinfunction "2_2") (pintype "passive"))
      (node (ref "R32") (pin "1") (pinfunction "1_1") (pintype "passive"))
    )
    (net (code "65") (name "Net-(R37-Pad1)") (class "Default")
      (node (ref "R37") (pin "1") (pinfunction "1_1") (pintype "passive"))
      (node (ref "VR3A") (pin "2") (pinfunction "2_2") (pintype "passive"))
      (node (ref "VR3A") (pin "3") (pinfunction "3_3") (pintype "passive"))
    )
    (net (code "66") (name "Net-(SW1-P)") (class "Default")
      (node (ref "R17") (pin "1") (pinfunction "1_1") (pintype "passive"))
      (node (ref "SW1") (pin "1") (pinfunction "P_1") (pintype "passive"))
    )
    (net (code "67") (name "VB") (class "Default")
      (node (ref "C2") (pin "+") (pinfunction "+_+") (pintype "passive"))
      (node (ref "R10") (pin "2") (pinfunction "2_2") (pintype "passive"))
      (node (ref "R14") (pin "1") (pinfunction "1_1") (pintype "passive"))
      (node (ref "R16") (pin "2") (pinfunction "2_2") (pintype "passive"))
      (node (ref "R19") (pin "2") (pinfunction "2_2") (pintype "passive"))
      (node (ref "R33") (pin "2") (pinfunction "2_2") (pintype "passive"))
      (node (ref "R35") (pin "1") (pinfunction "1_1") (pintype "passive"))
      (node (ref "R36") (pin "1") (pinfunction "1_1") (pintype "passive"))
      (node (ref "R40") (pin "1") (pinfunction "1_1") (pintype "passive"))
      (node (ref "R41") (pin "2") (pinfunction "2_2") (pintype "passive"))
      (node (ref "R45") (pin "2") (pinfunction "2_2") (pintype "passive"))
      (node (ref "R46") (pin "1") (pinfunction "1_1") (pintype "passive"))
      (node (ref "R8") (pin "2") (pinfunction "2_2") (pintype "passive"))
      (node (ref "R9") (pin "1") (pinfunction "1_1") (pintype "passive"))
      (node (ref "VR1") (pin "1") (pinfunction "1_1") (pintype "passive"))
    )
  )
)
